# 2_rs485v4.net
KiCad netlist of a schematic drawn in Altium Designer
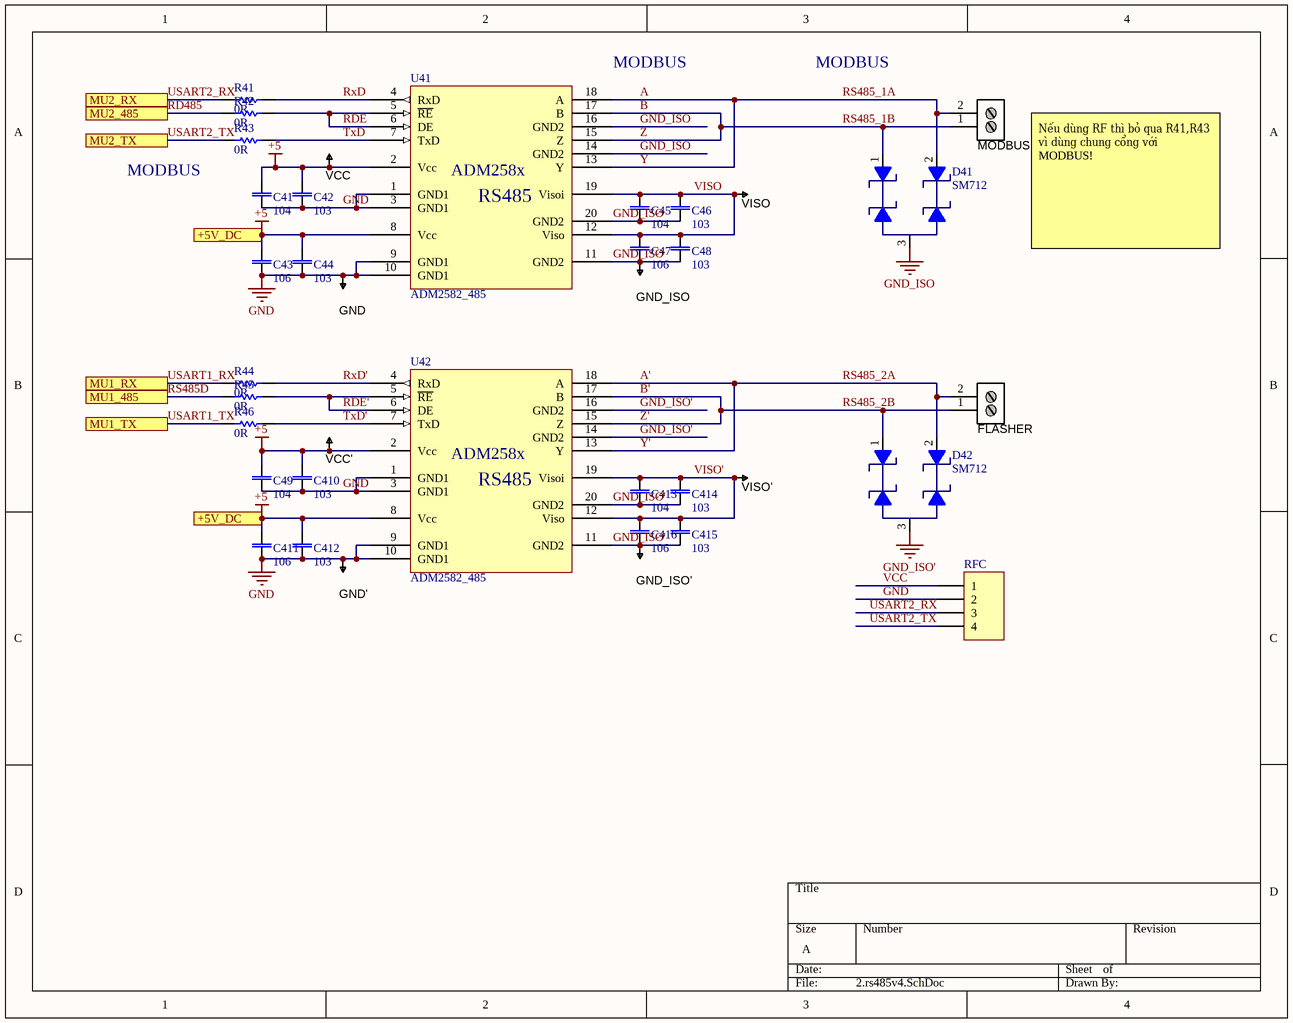
[diagram p0: 2.rs485v4.SchDoc]

(export (version "E")
  (design (tool "Eeschema 10.0.6"))
  (components
    (comp (ref "C41")
      (value "104")
      (footprint "swatpcblib:CAP 0805")
      (description "Capacitor non polarized")
      (fields (field (name "Comment") "Tụ điện dán 0805104"))
      (libsource (lib "swatpcblib") (part "CAP NP"))
    )
    (comp (ref "C42")
      (value "103")
      (footprint "swatpcblib:CAP 0805")
      (description "Capacitor non polarized")
      (fields (field (name "Comment") "Tụ điện dán 0805103"))
      (libsource (lib "swatpcblib") (part "CAP NP"))
    )
    (comp (ref "C43")
      (value "106")
      (footprint "swatpcblib:CAP 0805")
      (description "Capacitor non polarized")
      (fields (field (name "Comment") "Tụ điện dán 0805106"))
      (libsource (lib "swatpcblib") (part "CAP NP"))
    )
    (comp (ref "C44")
      (value "103")
      (footprint "swatpcblib:CAP 0805")
      (description "Capacitor non polarized")
      (fields (field (name "Comment") "Tụ điện dán 0805103"))
      (libsource (lib "swatpcblib") (part "CAP NP"))
    )
    (comp (ref "C45")
      (value "104")
      (footprint "swatpcblib:CAP 0805")
      (description "Capacitor non polarized")
      (fields (field (name "Comment") "Tụ điện dán 0805104"))
      (libsource (lib "swatpcblib") (part "CAP NP"))
    )
    (comp (ref "C46")
      (value "103")
      (footprint "swatpcblib:CAP 0805")
      (description "Capacitor non polarized")
      (fields (field (name "Comment") "Tụ điện dán 0805103"))
      (libsource (lib "swatpcblib") (part "CAP NP"))
    )
    (comp (ref "C47")
      (value "106")
      (footprint "swatpcblib:CAP 0805")
      (description "Capacitor non polarized")
      (fields (field (name "Comment") "Tụ điện dán 0805106"))
      (libsource (lib "swatpcblib") (part "CAP NP"))
    )
    (comp (ref "C48")
      (value "103")
      (footprint "swatpcblib:CAP 0805")
      (description "Capacitor non polarized")
      (fields (field (name "Comment") "Tụ điện dán 0805103"))
      (libsource (lib "swatpcblib") (part "CAP NP"))
    )
    (comp (ref "C49")
      (value "104")
      (footprint "swatpcblib:CAP 0805")
      (description "Capacitor non polarized")
      (fields (field (name "Comment") "Tụ điện dán 0805104"))
      (libsource (lib "swatpcblib") (part "CAP NP"))
    )
    (comp (ref "C410")
      (value "103")
      (footprint "swatpcblib:CAP 0805")
      (description "Capacitor non polarized")
      (fields (field (name "Comment") "Tụ điện dán 0805103"))
      (libsource (lib "swatpcblib") (part "CAP NP"))
    )
    (comp (ref "C411")
      (value "106")
      (footprint "swatpcblib:CAP 0805")
      (description "Capacitor non polarized")
      (fields (field (name "Comment") "Tụ điện dán 0805106"))
      (libsource (lib "swatpcblib") (part "CAP NP"))
    )
    (comp (ref "C412")
      (value "103")
      (footprint "swatpcblib:CAP 0805")
      (description "Capacitor non polarized")
      (fields (field (name "Comment") "Tụ điện dán 0805103"))
      (libsource (lib "swatpcblib") (part "CAP NP"))
    )
    (comp (ref "C413")
      (value "104")
      (footprint "swatpcblib:CAP 0805")
      (description "Capacitor non polarized")
      (fields (field (name "Comment") "Tụ điện dán 0805104"))
      (libsource (lib "swatpcblib") (part "CAP NP"))
    )
    (comp (ref "C414")
      (value "103")
      (footprint "swatpcblib:CAP 0805")
      (description "Capacitor non polarized")
      (fields (field (name "Comment") "Tụ điện dán 0805103"))
      (libsource (lib "swatpcblib") (part "CAP NP"))
    )
    (comp (ref "C415")
      (value "103")
      (footprint "swatpcblib:CAP 0805")
      (description "Capacitor non polarized")
      (fields (field (name "Comment") "Tụ điện dán 0805103"))
      (libsource (lib "swatpcblib") (part "CAP NP"))
    )
    (comp (ref "C416")
      (value "106")
      (footprint "swatpcblib:CAP 0805")
      (description "Capacitor non polarized")
      (fields (field (name "Comment") "Tụ điện dán 0805106"))
      (libsource (lib "swatpcblib") (part "CAP NP"))
    )
    (comp (ref "D41") (value "SM712") (footprint "SOT23 TOP") (libsource (lib "Tuan") (part "SM712")))
    (comp (ref "D42") (value "SM712") (footprint "SOT23 TOP") (libsource (lib "Tuan") (part "SM712")))
    (comp (ref "FLASHER")
      (value "Giắc xanh 5.08mm")
      (footprint "2P_PCB1")
      (description "Terminal Block Screw Type THT 2-Position 3.81mm pitch")
      (libsource (lib "PBL - Connectors") (part "2P_ScrewTerm_90S_3.81MM"))
    )
    (comp (ref "GND")
      (value "TESTPOINT")
      (footprint "TP-R60")
      (description "SMD test pin")
      (libsource (lib "PBL - Test Points") (part "TESTPOINT"))
    )
    (comp (ref "GND'")
      (value "TESTPOINT")
      (footprint "TP-R60")
      (description "SMD test pin")
      (libsource (lib "PBL - Test Points") (part "TESTPOINT"))
    )
    (comp (ref "GND_ISO")
      (value "TESTPOINT")
      (footprint "TP-R60")
      (description "SMD test pin")
      (libsource (lib "PBL - Test Points") (part "TESTPOINT"))
    )
    (comp (ref "GND_ISO'")
      (value "TESTPOINT")
      (footprint "TP-R60")
      (description "SMD test pin")
      (libsource (lib "PBL - Test Points") (part "TESTPOINT"))
    )
    (comp (ref "MODBUS")
      (value "Giắc xanh 5.08mm")
      (footprint "2P_PCB1")
      (description "Terminal Block Screw Type THT 2-Position 3.81mm pitch")
      (libsource (lib "PBL - Connectors") (part "2P_ScrewTerm_90S_3.81MM"))
    )
    (comp (ref "R41")
      (value "0R")
      (footprint "swatpcblib:RES 0805")
      (description "Resistor")
      (fields (field (name "Comment") "Điện trở dán 08050R"))
      (libsource (lib "swatpcblib") (part "Res"))
    )
    (comp (ref "R42")
      (value "0R")
      (footprint "swatpcblib:RES 0805")
      (description "Resistor")
      (fields (field (name "Comment") "Điện trở dán 08050R"))
      (libsource (lib "swatpcblib") (part "Res"))
    )
    (comp (ref "R43")
      (value "0R")
      (footprint "swatpcblib:RES 0805")
      (description "Resistor")
      (fields (field (name "Comment") "Điện trở dán 08050R"))
      (libsource (lib "swatpcblib") (part "Res"))
    )
    (comp (ref "R44")
      (value "0R")
      (footprint "swatpcblib:RES 0805")
      (description "Resistor")
      (fields (field (name "Comment") "Điện trở dán 08050R"))
      (libsource (lib "swatpcblib") (part "Res"))
    )
    (comp (ref "R45")
      (value "0R")
      (footprint "swatpcblib:RES 0805")
      (description "Resistor")
      (fields (field (name "Comment") "Điện trở dán 08050R"))
      (libsource (lib "swatpcblib") (part "Res"))
    )
    (comp (ref "R46")
      (value "0R")
      (footprint "swatpcblib:RES 0805")
      (description "Resistor")
      (fields (field (name "Comment") "Điện trở dán 08050R"))
      (libsource (lib "swatpcblib") (part "Res"))
    )
    (comp (ref "RFC")
      (value "Header 4")
      (footprint "HDR1X4")
      (description "Header, 4-Pin")
      (fields (field (name "PUBLISHER") "Altium Limited"))
      (libsource (lib "Miscellaneous Connectors") (part "Header 4"))
    )
    (comp (ref "U41")
      (value "ADM2582_485")
      (footprint "syhaunguyen:SO-20B")
      (libsource (lib "Tuan") (part "ADM2582_485"))
    )
    (comp (ref "U42")
      (value "ADM2582_485")
      (footprint "syhaunguyen:SO-20B")
      (libsource (lib "Tuan") (part "ADM2582_485"))
    )
    (comp (ref "VCC")
      (value "TESTPOINT")
      (footprint "TP-R60")
      (description "SMD test pin")
      (libsource (lib "PBL - Test Points") (part "TESTPOINT"))
    )
    (comp (ref "VCC'")
      (value "TESTPOINT")
      (footprint "TP-R60")
      (description "SMD test pin")
      (libsource (lib "PBL - Test Points") (part "TESTPOINT"))
    )
    (comp (ref "VISO")
      (value "TESTPOINT")
      (footprint "TP-R60")
      (description "SMD test pin")
      (libsource (lib "PBL - Test Points") (part "TESTPOINT"))
    )
    (comp (ref "VISO'")
      (value "TESTPOINT")
      (footprint "TP-R60")
      (description "SMD test pin")
      (libsource (lib "PBL - Test Points") (part "TESTPOINT"))
    )
  )
  (nets
    (net (code "1") (name "+5") (class "Default")
      (node (ref "C41") (pin "2") (pinfunction "2_2") (pintype "passive"))
      (node (ref "C410") (pin "2") (pinfunction "2_2") (pintype "passive"))
      (node (ref "C411") (pin "2") (pinfunction "2_2") (pintype "passive"))
      (node (ref "C412") (pin "2") (pinfunction "2_2") (pintype "passive"))
      (node (ref "C42") (pin "2") (pinfunction "2_2") (pintype "passive"))
      (node (ref "C43") (pin "2") (pinfunction "2_2") (pintype "passive"))
      (node (ref "C44") (pin "2") (pinfunction "2_2") (pintype "passive"))
      (node (ref "C49") (pin "2") (pinfunction "2_2") (pintype "passive"))
      (node (ref "U41") (pin "2") (pinfunction "Vcc_2") (pintype "power_in"))
      (node (ref "U41") (pin "8") (pinfunction "Vcc_8") (pintype "power_in"))
      (node (ref "U42") (pin "2") (pinfunction "Vcc_2") (pintype "power_in"))
      (node (ref "U42") (pin "8") (pinfunction "Vcc_8") (pintype "power_in"))
      (node (ref "VCC") (pin "1") (pintype "passive"))
      (node (ref "VCC'") (pin "1") (pintype "passive"))
    )
    (net (code "2") (name "/A") (class "Default")
      (node (ref "D41") (pin "2") (pinfunction "IO2_2") (pintype "passive"))
      (node (ref "MODBUS") (pin "2") (pinfunction "2_2") (pintype "passive"))
      (node (ref "U41") (pin "13") (pinfunction "Y_13") (pintype "passive"))
      (node (ref "U41") (pin "18") (pinfunction "A_18") (pintype "passive"))
    )
    (net (code "3") (name "/A'") (class "Default")
      (node (ref "D42") (pin "2") (pinfunction "IO2_2") (pintype "passive"))
      (node (ref "FLASHER") (pin "2") (pinfunction "2_2") (pintype "passive"))
      (node (ref "U42") (pin "13") (pinfunction "Y_13") (pintype "passive"))
      (node (ref "U42") (pin "18") (pinfunction "A_18") (pintype "passive"))
    )
    (net (code "4") (name "/B") (class "Default")
      (node (ref "D41") (pin "1") (pinfunction "IO1_1") (pintype "passive"))
      (node (ref "MODBUS") (pin "1") (pinfunction "1_1") (pintype "passive"))
      (node (ref "U41") (pin "15") (pinfunction "Z_15") (pintype "passive"))
      (node (ref "U41") (pin "17") (pinfunction "B_17") (pintype "passive"))
    )
    (net (code "5") (name "/B'") (class "Default")
      (node (ref "D42") (pin "1") (pinfunction "IO1_1") (pintype "passive"))
      (node (ref "FLASHER") (pin "1") (pinfunction "1_1") (pintype "passive"))
      (node (ref "U42") (pin "15") (pinfunction "Z_15") (pintype "passive"))
      (node (ref "U42") (pin "17") (pinfunction "B_17") (pintype "passive"))
    )
    (net (code "6") (name "/RD485") (class "Default")
      (node (ref "R42") (pin "1") (pinfunction "1_1") (pintype "passive"))
    )
    (net (code "7") (name "/RDE") (class "Default")
      (node (ref "R42") (pin "2") (pinfunction "2_2") (pintype "passive"))
      (node (ref "U41") (pin "5") (pinfunction "~{RE}_5") (pintype "input"))
      (node (ref "U41") (pin "6") (pinfunction "DE_6") (pintype "input"))
    )
    (net (code "8") (name "/RDE'") (class "Default")
      (node (ref "R45") (pin "2") (pinfunction "2_2") (pintype "passive"))
      (node (ref "U42") (pin "5") (pinfunction "~{RE}_5") (pintype "input"))
      (node (ref "U42") (pin "6") (pinfunction "DE_6") (pintype "input"))
    )
    (net (code "9") (name "/RS485D") (class "Default")
      (node (ref "R45") (pin "1") (pinfunction "1_1") (pintype "passive"))
    )
    (net (code "10") (name "/RxD") (class "Default")
      (node (ref "R41") (pin "2") (pinfunction "2_2") (pintype "passive"))
      (node (ref "U41") (pin "4") (pinfunction "RxD_4") (pintype "output"))
    )
    (net (code "11") (name "/RxD'") (class "Default")
      (node (ref "R44") (pin "2") (pinfunction "2_2") (pintype "passive"))
      (node (ref "U42") (pin "4") (pinfunction "RxD_4") (pintype "output"))
    )
    (net (code "12") (name "/TxD") (class "Default")
      (node (ref "R43") (pin "2") (pinfunction "2_2") (pintype "passive"))
      (node (ref "U41") (pin "7") (pinfunction "TxD_7") (pintype "input"))
    )
    (net (code "13") (name "/TxD'") (class "Default")
      (node (ref "R46") (pin "2") (pinfunction "2_2") (pintype "passive"))
      (node (ref "U42") (pin "7") (pinfunction "TxD_7") (pintype "input"))
    )
    (net (code "14") (name "/USART1_RX") (class "Default")
      (node (ref "R44") (pin "1") (pinfunction "1_1") (pintype "passive"))
    )
    (net (code "15") (name "/USART1_TX") (class "Default")
      (node (ref "R46") (pin "1") (pinfunction "1_1") (pintype "passive"))
    )
    (net (code "16") (name "/USART2_RX") (class "Default")
      (node (ref "R41") (pin "1") (pinfunction "1_1") (pintype "passive"))
      (node (ref "RFC") (pin "3") (pinfunction "3_3") (pintype "passive"))
    )
    (net (code "17") (name "/USART2_TX") (class "Default")
      (node (ref "R43") (pin "1") (pinfunction "1_1") (pintype "passive"))
      (node (ref "RFC") (pin "4") (pinfunction "4_4") (pintype "passive"))
    )
    (net (code "18") (name "/VCC") (class "Default")
      (node (ref "RFC") (pin "1") (pinfunction "1_1") (pintype "passive"))
    )
    (net (code "19") (name "/VISO") (class "Default")
      (node (ref "C45") (pin "2") (pinfunction "2_2") (pintype "passive"))
      (node (ref "C46") (pin "2") (pinfunction "2_2") (pintype "passive"))
      (node (ref "C47") (pin "2") (pinfunction "2_2") (pintype "passive"))
      (node (ref "C48") (pin "2") (pinfunction "2_2") (pintype "passive"))
      (node (ref "U41") (pin "12") (pinfunction "Viso_12") (pintype "power_in"))
      (node (ref "U41") (pin "19") (pinfunction "Visoi_19") (pintype "power_in"))
      (node (ref "VISO") (pin "1") (pintype "passive"))
    )
    (net (code "20") (name "/VISO'") (class "Default")
      (node (ref "C413") (pin "2") (pinfunction "2_2") (pintype "passive"))
      (node (ref "C414") (pin "2") (pinfunction "2_2") (pintype "passive"))
      (node (ref "C415") (pin "2") (pinfunction "2_2") (pintype "passive"))
      (node (ref "C416") (pin "2") (pinfunction "2_2") (pintype "passive"))
      (node (ref "U42") (pin "12") (pinfunction "Viso_12") (pintype "power_in"))
      (node (ref "U42") (pin "19") (pinfunction "Visoi_19") (pintype "power_in"))
      (node (ref "VISO'") (pin "1") (pintype "passive"))
    )
    (net (code "21") (name "GND") (class "Default")
      (node (ref "C41") (pin "1") (pinfunction "1_1") (pintype "passive"))
      (node (ref "C410") (pin "1") (pinfunction "1_1") (pintype "passive"))
      (node (ref "C411") (pin "1") (pinfunction "1_1") (pintype "passive"))
      (node (ref "C412") (pin "1") (pinfunction "1_1") (pintype "passive"))
      (node (ref "C42") (pin "1") (pinfunction "1_1") (pintype "passive"))
      (node (ref "C43") (pin "1") (pinfunction "1_1") (pintype "passive"))
      (node (ref "C44") (pin "1") (pinfunction "1_1") (pintype "passive"))
      (node (ref "C49") (pin "1") (pinfunction "1_1") (pintype "passive"))
      (node (ref "GND") (pin "1") (pintype "passive"))
      (node (ref "GND'") (pin "1") (pintype "passive"))
      (node (ref "RFC") (pin "2") (pinfunction "2_2") (pintype "passive"))
      (node (ref "U41") (pin "1") (pinfunction "GND1_1") (pintype "power_in"))
      (node (ref "U41") (pin "10") (pinfunction "GND1_10") (pintype "power_in"))
      (node (ref "U41") (pin "3") (pinfunction "GND1_3") (pintype "power_in"))
      (node (ref "U41") (pin "9") (pinfunction "GND1_9") (pintype "power_in"))
      (node (ref "U42") (pin "1") (pinfunction "GND1_1") (pintype "power_in"))
      (node (ref "U42") (pin "10") (pinfunction "GND1_10") (pintype "power_in"))
      (node (ref "U42") (pin "3") (pinfunction "GND1_3") (pintype "power_in"))
      (node (ref "U42") (pin "9") (pinfunction "GND1_9") (pintype "power_in"))
    )
    (net (code "22") (name "GND_ISO") (class "Default")
      (node (ref "C45") (pin "1") (pinfunction "1_1") (pintype "passive"))
      (node (ref "C46") (pin "1") (pinfunction "1_1") (pintype "passive"))
      (node (ref "C47") (pin "1") (pinfunction "1_1") (pintype "passive"))
      (node (ref "C48") (pin "1") (pinfunction "1_1") (pintype "passive"))
      (node (ref "D41") (pin "3") (pinfunction "GND_3") (pintype "passive"))
      (node (ref "GND_ISO") (pin "1") (pintype "passive"))
      (node (ref "U41") (pin "11") (pinfunction "GND2_11") (pintype "power_in"))
      (node (ref "U41") (pin "14") (pinfunction "GND2_14") (pintype "power_in"))
      (node (ref "U41") (pin "16") (pinfunction "GND2_16") (pintype "power_in"))
      (node (ref "U41") (pin "20") (pinfunction "GND2_20") (pintype "power_in"))
    )
    (net (code "23") (name "GND_ISO'") (class "Default")
      (node (ref "C413") (pin "1") (pinfunction "1_1") (pintype "passive"))
      (node (ref "C414") (pin "1") (pinfunction "1_1") (pintype "passive"))
      (node (ref "C415") (pin "1") (pinfunction "1_1") (pintype "passive"))
      (node (ref "C416") (pin "1") (pinfunction "1_1") (pintype "passive"))
      (node (ref "D42") (pin "3") (pinfunction "GND_3") (pintype "passive"))
      (node (ref "GND_ISO'") (pin "1") (pintype "passive"))
      (node (ref "U42") (pin "11") (pinfunction "GND2_11") (pintype "power_in"))
      (node (ref "U42") (pin "14") (pinfunction "GND2_14") (pintype "power_in"))
      (node (ref "U42") (pin "16") (pinfunction "GND2_16") (pintype "power_in"))
      (node (ref "U42") (pin "20") (pinfunction "GND2_20") (pintype "power_in"))
    )
  )
)
